# Poactuator_Connectors.net
KiCad netlist of a schematic drawn in Altium Designer
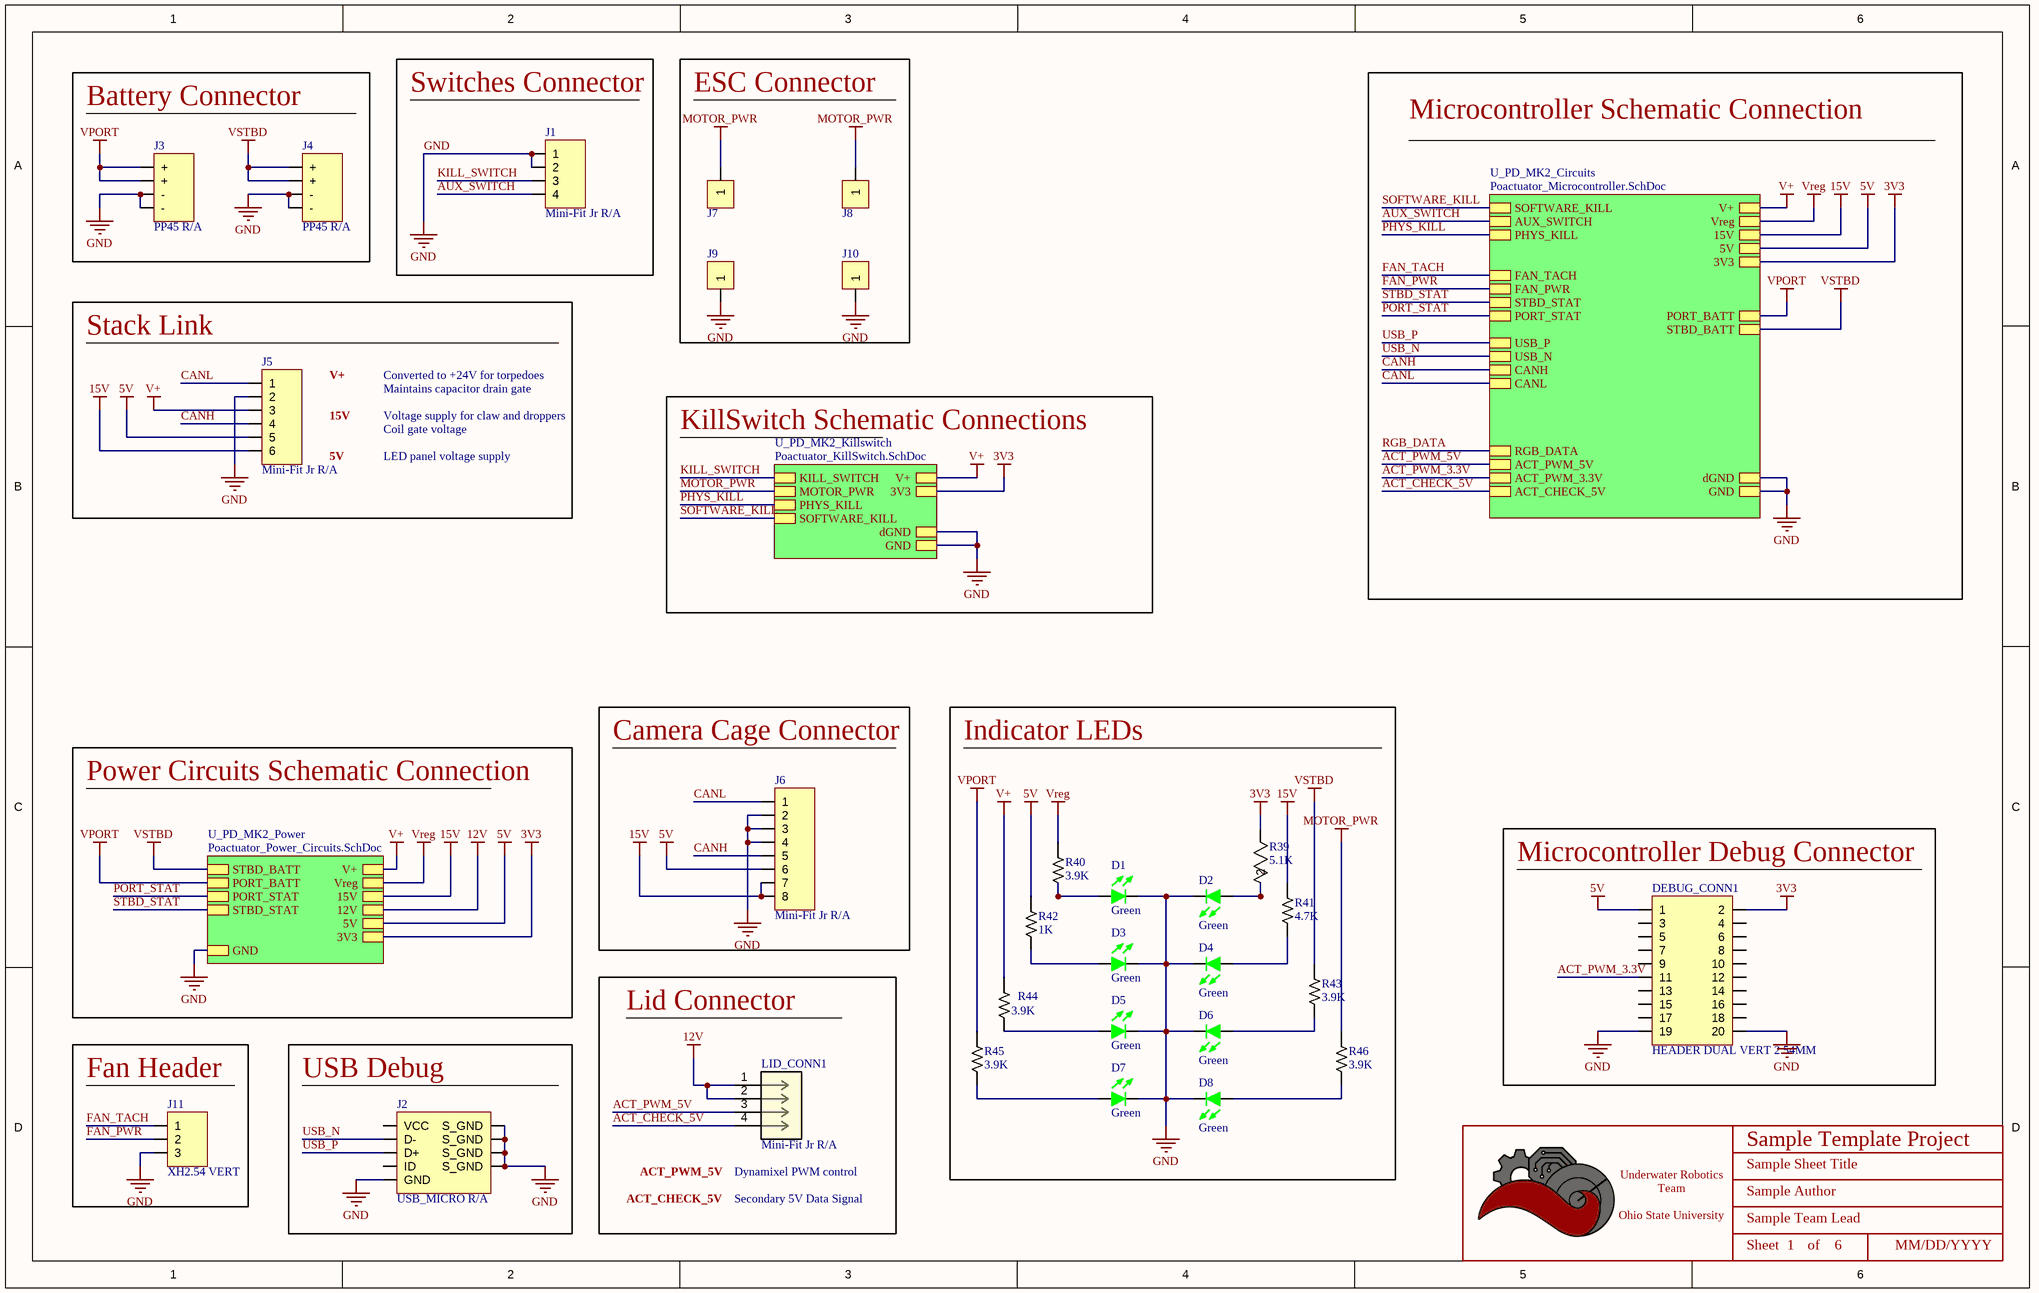
[diagram p0: Poactuator_Connectors.SchDoc]

(export (version "E")
  (design (tool "Eeschema 10.0.6"))
  (components
    (comp (ref "D1")
      (value "IN-S63AT5G")
      (footprint "LED_0603")
      (description "LED Green Vf= 3V If = 0.005A\r\nIN-S63AT5G")
      (fields (field (name "COLOR") "Green") (field (name "MADE BY") "Robert Pafford"))
      (libsource (lib "Diodes") (part "LED_Green_0603_3V"))
    )
    (comp (ref "D2")
      (value "IN-S63AT5G")
      (footprint "LED_0603")
      (description "LED Green Vf= 3V If = 0.005A\r\nIN-S63AT5G")
      (fields (field (name "COLOR") "Green") (field (name "MADE BY") "Robert Pafford"))
      (libsource (lib "Diodes") (part "LED_Green_0603_3V"))
    )
    (comp (ref "D3")
      (value "IN-S63AT5G")
      (footprint "LED_0603")
      (description "LED Green Vf= 3V If = 0.005A\r\nIN-S63AT5G")
      (fields (field (name "COLOR") "Green") (field (name "MADE BY") "Robert Pafford"))
      (libsource (lib "Diodes") (part "LED_Green_0603_3V"))
    )
    (comp (ref "D4")
      (value "IN-S63AT5G")
      (footprint "LED_0603")
      (description "LED Green Vf= 3V If = 0.005A\r\nIN-S63AT5G")
      (fields (field (name "COLOR") "Green") (field (name "MADE BY") "Robert Pafford"))
      (libsource (lib "Diodes") (part "LED_Green_0603_3V"))
    )
    (comp (ref "D5")
      (value "IN-S63AT5G")
      (footprint "LED_0603")
      (description "LED Green Vf= 3V If = 0.005A\r\nIN-S63AT5G")
      (fields (field (name "COLOR") "Green") (field (name "MADE BY") "Robert Pafford"))
      (libsource (lib "Diodes") (part "LED_Green_0603_3V"))
    )
    (comp (ref "D6")
      (value "IN-S63AT5G")
      (footprint "LED_0603")
      (description "LED Green Vf= 3V If = 0.005A\r\nIN-S63AT5G")
      (fields (field (name "COLOR") "Green") (field (name "MADE BY") "Robert Pafford"))
      (libsource (lib "Diodes") (part "LED_Green_0603_3V"))
    )
    (comp (ref "D7")
      (value "IN-S63AT5G")
      (footprint "LED_0603")
      (description "LED Green Vf= 3V If = 0.005A\r\nIN-S63AT5G")
      (fields (field (name "COLOR") "Green") (field (name "MADE BY") "Robert Pafford"))
      (libsource (lib "Diodes") (part "LED_Green_0603_3V"))
    )
    (comp (ref "D8")
      (value "IN-S63AT5G")
      (footprint "LED_0603")
      (description "LED Green Vf= 3V If = 0.005A\r\nIN-S63AT5G")
      (fields (field (name "COLOR") "Green") (field (name "MADE BY") "Robert Pafford"))
      (libsource (lib "Diodes") (part "LED_Green_0603_3V"))
    )
    (comp (ref "DEBUG_CONN1")
      (value "HEADER DUAL VERT 2.54MM")
      (footprint "HEADER_2x10PIN_2.54MM")
      (description "CONN HEADER VERT 20POS 2.54MM")
      (fields (field (name "MADE BY") "Tyson Nguyen"))
      (libsource (lib "Connectors") (part "HEADER_2x10PIN_2.54MM"))
    )
    (comp (ref "J1")
      (value "Mini-Fit Jr R/A")
      (footprint "CONN_MOLEX_MINIFIT JR_4 POS_R/A")
      (description "Molex Minifit Jr. 5569 \r\n4 Pos R/A Natural")
      (fields (field (name "MANUFACTURER") "Molex") (field (name "CREATED BY") "Flip B"))
      (libsource (lib "Connectors") (part "CONN_MOLEX_MINIFIT JR_4POS_R/A"))
    )
    (comp (ref "J2")
      (value "USB_MICRO R/A")
      (footprint "CONN_MINIUSB")
      (description "Amphenol Micro USB-B\r\nUSB2.0 5 Pin Right Angle SMD")
      (fields (field (name "MANUFACTURER") "Amphenol") (field (name "CREATED BY") "Flip B"))
      (libsource (lib "Connectors") (part "CONN_MICROUSB"))
    )
    (comp (ref "J3")
      (value "PP45 R/A")
      (footprint "CONN_ANDERSON_PP45_4 POS_R/A")
      (description "Anderson PP45\r\n4 Pos R/A Red/Black")
      (fields (field (name "MANUFACTURER") "Anderson") (field (name "CREATED BY") "Flip B"))
      (libsource (lib "Connectors") (part "CONN_ANDERSON_2x2_R/A"))
    )
    (comp (ref "J4")
      (value "PP45 R/A")
      (footprint "CONN_ANDERSON_PP45_4 POS_R/A")
      (description "Anderson PP45\r\n4 Pos R/A Red/Black")
      (fields (field (name "MANUFACTURER") "Anderson") (field (name "CREATED BY") "Flip B"))
      (libsource (lib "Connectors") (part "CONN_ANDERSON_2x2_R/A"))
    )
    (comp (ref "J5")
      (value "Mini-Fit Jr R/A")
      (footprint "CONN_MOLEX_MINIFIT JR_6 POS_R/A")
      (description "Molex Minifit Jr. 5569 \r\n6 Pos R/A Natural")
      (fields (field (name "MANUFACTURER") "Molex") (field (name "CREATED BY") "Flip B"))
      (libsource (lib "Connectors") (part "CONN_MOLEX_MINIFIT JR_6POS_R/A"))
    )
    (comp (ref "J6")
      (value "Mini-Fit Jr R/A")
      (footprint "CONN_MOLEX_MINIFIT JR_8 POS_R/A")
      (description "Molex Minifit Jr. 5569 \r\n8 Pos R/A Natural")
      (fields (field (name "MANUFACTURER") "Molex") (field (name "CREATED BY") "Flip B"))
      (libsource (lib "Connectors") (part "CONN_MOLEX_MINIFIT JR_8POS_R/A"))
    )
    (comp (ref "J7")
      (value "Redcube M4 Term 85A")
      (footprint "Redcube M4 Term 85A")
      (fields (field (name "CREATED BY") "Nahtan Ayer"))
      (libsource (lib "") (part "Redcube M4 Term 85A_1"))
    )
    (comp (ref "J8")
      (value "Redcube M4 Term 85A")
      (footprint "Redcube M4 Term 85A")
      (fields (field (name "CREATED BY") "Nahtan Ayer"))
      (libsource (lib "") (part "Redcube M4 Term 85A_1"))
    )
    (comp (ref "J9")
      (value "Redcube M4 Term 85A")
      (footprint "Redcube M4 Term 85A")
      (fields (field (name "CREATED BY") "Nahtan Ayer"))
      (libsource (lib "Connectors") (part "Redcube M4 Term 85A"))
    )
    (comp (ref "J10")
      (value "Redcube M4 Term 85A")
      (footprint "Redcube M4 Term 85A")
      (fields (field (name "CREATED BY") "Nahtan Ayer"))
      (libsource (lib "Connectors") (part "Redcube M4 Term 85A"))
    )
    (comp (ref "J11")
      (value "XH2.54 VERT")
      (footprint "CONN_JST_XH254_3POS_VERT")
      (description "JST XH 2.54mm Pitch 3 Pos Vertical")
      (fields (field (name "MANUFACTURER") "JST") (field (name "CREATED BY") "Robert P"))
      (libsource (lib "Connectors") (part "CONN_JST_XH254_3POS_VERT"))
    )
    (comp (ref "LID_CONN1")
      (value "Mini-Fit Jr R/A")
      (footprint "CONN HEADER R/A 4POS 4.2MM")
      (description "Mini-Fit Jr Connector Header Through Hole, Right Angle 4 position 0.165\" (4.20mm)")
      (fields (field (name "MANUFACTURER") "Molex") (field (name "CREATED BY") "Zach Ramsey"))
      (libsource (lib "Connectors") (part "CONN HEADER R/A 4POS 4.2MM"))
    )
    (comp (ref "R39")
      (value "5.1K")
      (footprint "RC0603N_PAN")
      (description "5.1 kOhms ±0.1% 0.1W, 1/10W Chip Resistor 0603 (1608 Metric) Automotive AEC-Q200 Thin Film")
      (fields
        (field (name "MANUFACTURER_PART_NUMBER") "ERA-3AEB512V_2")
        (field (name "COPYRIGHT") "Copyright (C) 2023 Ultra Librarian. All rights reserved.")
      )
      (libsource (lib "Resistors") (part "ERA-3AEB512V_2"))
    )
    (comp (ref "R40")
      (value "3.9k Ohm 5% 1/10W")
      (footprint "RESISTOR_0603")
      (description "RES 3.9k OHM 1% 1/10W 0603")
      (fields
        (field (name "TOLERANCE") "+/- 1%")
        (field (name "VALUE  (OHMS)") "3.9K")
        (field (name "MADE BY") "Robert Pafford")
      )
      (libsource (lib "Resistors") (part "RESISTOR_3.9K_0603"))
    )
    (comp (ref "R41")
      (value "4.7k Ohm 5% 1/10W")
      (footprint "RESISTOR_0603")
      (description "RES 4.7k OHM 5% 1/10W 0603")
      (fields
        (field (name "TOLERANCE") "+/- 5%")
        (field (name "VALUE  (OHMS)") "4.7K")
        (field (name "MADE BY") "Robert Pafford")
      )
      (libsource (lib "Resistors") (part "RESISTOR_4.7K_0603"))
    )
    (comp (ref "R42")
      (value "1k Ohm 5% 1/8W")
      (footprint "RESISTOR_0603")
      (description "RES 1k OHM 5% 1/8W 0603")
      (fields
        (field (name "TOLERANCE") "+/- 5%")
        (field (name "VALUE  (OHMS)") "1K")
        (field (name "MADE BY") "Robert Pafford")
      )
      (libsource (lib "Resistors") (part "RESISTOR_1K_0603"))
    )
    (comp (ref "R43")
      (value "3.9k Ohm 5% 1/10W")
      (footprint "RESISTOR_0603")
      (description "RES 3.9k OHM 1% 1/10W 0603")
      (fields
        (field (name "TOLERANCE") "+/- 1%")
        (field (name "VALUE  (OHMS)") "3.9K")
        (field (name "MADE BY") "Robert Pafford")
      )
      (libsource (lib "Resistors") (part "RESISTOR_3.9K_0603"))
    )
    (comp (ref "R44")
      (value "3.9k Ohm 5% 1/10W")
      (footprint "RESISTOR_0603")
      (description "RES 3.9k OHM 1% 1/10W 0603")
      (fields
        (field (name "TOLERANCE") "+/- 1%")
        (field (name "VALUE  (OHMS)") "3.9K")
        (field (name "MADE BY") "Robert Pafford")
      )
      (libsource (lib "Resistors") (part "RESISTOR_3.9K_0603"))
    )
    (comp (ref "R45")
      (value "3.9k Ohm 5% 1/10W")
      (footprint "RESISTOR_0603")
      (description "RES 3.9k OHM 1% 1/10W 0603")
      (fields
        (field (name "TOLERANCE") "+/- 1%")
        (field (name "VALUE  (OHMS)") "3.9K")
        (field (name "MADE BY") "Robert Pafford")
      )
      (libsource (lib "Resistors") (part "RESISTOR_3.9K_0603"))
    )
    (comp (ref "R46")
      (value "3.9k Ohm 5% 1/10W")
      (footprint "RESISTOR_0603")
      (description "RES 3.9k OHM 1% 1/10W 0603")
      (fields
        (field (name "TOLERANCE") "+/- 1%")
        (field (name "VALUE  (OHMS)") "3.9K")
        (field (name "MADE BY") "Robert Pafford")
      )
      (libsource (lib "Resistors") (part "RESISTOR_3.9K_0603"))
    )
  )
  (nets
    (net (code "1") (name "/ACT_CHECK_5V") (class "Default")
      (node (ref "LID_CONN1") (pin "4") (pinfunction "4_4") (pintype "passive"))
    )
    (net (code "2") (name "/ACT_PWM_3.3V") (class "Default")
      (node (ref "DEBUG_CONN1") (pin "11") (pinfunction "11_11") (pintype "passive"))
    )
    (net (code "3") (name "/ACT_PWM_5V") (class "Default")
      (node (ref "LID_CONN1") (pin "3") (pinfunction "3_3") (pintype "passive"))
    )
    (net (code "4") (name "/AUX_SWITCH") (class "Default")
      (node (ref "J1") (pin "4") (pinfunction "4_4") (pintype "passive"))
    )
    (net (code "5") (name "/CANH") (class "Default")
      (node (ref "J5") (pin "4") (pinfunction "4_4") (pintype "passive"))
      (node (ref "J6") (pin "5") (pinfunction "5_5") (pintype "passive"))
    )
    (net (code "6") (name "/CANL") (class "Default")
      (node (ref "J5") (pin "1") (pinfunction "1_1") (pintype "passive"))
      (node (ref "J6") (pin "1") (pinfunction "1_1") (pintype "passive"))
    )
    (net (code "7") (name "/FAN_PWR") (class "Default")
      (node (ref "J11") (pin "2") (pinfunction "2_2") (pintype "passive"))
    )
    (net (code "8") (name "/FAN_TACH") (class "Default")
      (node (ref "J11") (pin "1") (pinfunction "1_1") (pintype "passive"))
    )
    (net (code "9") (name "/KILL_SWITCH") (class "Default")
      (node (ref "J1") (pin "3") (pinfunction "3_3") (pintype "passive"))
    )
    (net (code "15") (name "/USB_N") (class "Default")
      (node (ref "J2") (pin "2") (pinfunction "D-_2") (pintype "passive"))
    )
    (net (code "16") (name "/USB_P") (class "Default")
      (node (ref "J2") (pin "3") (pinfunction "D+_3") (pintype "passive"))
    )
    (net (code "17") (name "3V3") (class "Default")
      (node (ref "DEBUG_CONN1") (pin "2") (pinfunction "2_2") (pintype "passive"))
      (node (ref "R39") (pin "1") (pinfunction "1_1") (pintype "passive"))
    )
    (net (code "18") (name "5V") (class "Default")
      (node (ref "DEBUG_CONN1") (pin "1") (pinfunction "1_1") (pintype "passive"))
      (node (ref "J5") (pin "5") (pinfunction "5_5") (pintype "passive"))
      (node (ref "J6") (pin "6") (pinfunction "6_6") (pintype "passive"))
      (node (ref "R42") (pin "1") (pinfunction "1_1") (pintype "passive"))
    )
    (net (code "19") (name "12V") (class "Default")
      (node (ref "LID_CONN1") (pin "1") (pinfunction "1_1") (pintype "passive"))
      (node (ref "LID_CONN1") (pin "2") (pinfunction "2_2") (pintype "passive"))
    )
    (net (code "20") (name "15V") (class "Default")
      (node (ref "J5") (pin "6") (pinfunction "6_6") (pintype "passive"))
      (node (ref "J6") (pin "7") (pinfunction "7_7") (pintype "passive"))
      (node (ref "J6") (pin "8") (pinfunction "8_8") (pintype "passive"))
      (node (ref "R41") (pin "1") (pinfunction "1_1") (pintype "passive"))
    )
    (net (code "21") (name "GND") (class "Default")
      (node (ref "D1") (pin "2") (pinfunction "2_2") (pintype "passive"))
      (node (ref "D2") (pin "2") (pinfunction "2_2") (pintype "passive"))
      (node (ref "D3") (pin "2") (pinfunction "2_2") (pintype "passive"))
      (node (ref "D4") (pin "2") (pinfunction "2_2") (pintype "passive"))
      (node (ref "D5") (pin "2") (pinfunction "2_2") (pintype "passive"))
      (node (ref "D6") (pin "2") (pinfunction "2_2") (pintype "passive"))
      (node (ref "D7") (pin "2") (pinfunction "2_2") (pintype "passive"))
      (node (ref "D8") (pin "2") (pinfunction "2_2") (pintype "passive"))
      (node (ref "DEBUG_CONN1") (pin "19") (pinfunction "19_19") (pintype "passive"))
      (node (ref "DEBUG_CONN1") (pin "20") (pinfunction "20_20") (pintype "passive"))
      (node (ref "J1") (pin "1") (pinfunction "1_1") (pintype "passive"))
      (node (ref "J1") (pin "2") (pinfunction "2_2") (pintype "passive"))
      (node (ref "J10") (pin "1") (pinfunction "1_1") (pintype "passive"))
      (node (ref "J11") (pin "3") (pinfunction "3_3") (pintype "passive"))
      (node (ref "J2") (pin "5") (pinfunction "GND_5") (pintype "passive"))
      (node (ref "J2") (pin "6") (pinfunction "S_GND_6") (pintype "passive"))
      (node (ref "J2") (pin "7") (pinfunction "S_GND_7") (pintype "passive"))
      (node (ref "J2") (pin "8") (pinfunction "S_GND_8") (pintype "passive"))
      (node (ref "J2") (pin "9") (pinfunction "S_GND_9") (pintype "passive"))
      (node (ref "J3") (pin "3") (pinfunction "-_3") (pintype "passive"))
      (node (ref "J3") (pin "4") (pinfunction "-_4") (pintype "passive"))
      (node (ref "J4") (pin "3") (pinfunction "-_3") (pintype "passive"))
      (node (ref "J4") (pin "4") (pinfunction "-_4") (pintype "passive"))
      (node (ref "J5") (pin "2") (pinfunction "2_2") (pintype "passive"))
      (node (ref "J6") (pin "2") (pinfunction "2_2") (pintype "passive"))
      (node (ref "J6") (pin "3") (pinfunction "3_3") (pintype "passive"))
      (node (ref "J6") (pin "4") (pinfunction "4_4") (pintype "passive"))
      (node (ref "J9") (pin "1") (pinfunction "1_1") (pintype "passive"))
    )
    (net (code "22") (name "MOTOR_PWR") (class "Default")
      (node (ref "J7") (pin "1") (pinfunction "1_1") (pintype "passive"))
      (node (ref "J8") (pin "1") (pinfunction "1_1") (pintype "passive"))
      (node (ref "R46") (pin "1") (pinfunction "1_1") (pintype "passive"))
    )
    (net (code "23") (name "Net-(D1-Pad1)") (class "Default")
      (node (ref "D1") (pin "1") (pinfunction "1_1") (pintype "passive"))
      (node (ref "R40") (pin "2") (pinfunction "2_2") (pintype "passive"))
    )
    (net (code "24") (name "Net-(D2-Pad1)") (class "Default")
      (node (ref "D2") (pin "1") (pinfunction "1_1") (pintype "passive"))
      (node (ref "R39") (pin "2") (pinfunction "2_2") (pintype "passive"))
    )
    (net (code "25") (name "Net-(D3-Pad1)") (class "Default")
      (node (ref "D3") (pin "1") (pinfunction "1_1") (pintype "passive"))
      (node (ref "R42") (pin "2") (pinfunction "2_2") (pintype "passive"))
    )
    (net (code "26") (name "Net-(D4-Pad1)") (class "Default")
      (node (ref "D4") (pin "1") (pinfunction "1_1") (pintype "passive"))
      (node (ref "R41") (pin "2") (pinfunction "2_2") (pintype "passive"))
    )
    (net (code "27") (name "Net-(D5-Pad1)") (class "Default")
      (node (ref "D5") (pin "1") (pinfunction "1_1") (pintype "passive"))
      (node (ref "R44") (pin "2") (pinfunction "2_2") (pintype "passive"))
    )
    (net (code "28") (name "Net-(D6-Pad1)") (class "Default")
      (node (ref "D6") (pin "1") (pinfunction "1_1") (pintype "passive"))
      (node (ref "R43") (pin "2") (pinfunction "2_2") (pintype "passive"))
    )
    (net (code "29") (name "Net-(D7-Pad1)") (class "Default")
      (node (ref "D7") (pin "1") (pinfunction "1_1") (pintype "passive"))
      (node (ref "R45") (pin "2") (pinfunction "2_2") (pintype "passive"))
    )
    (net (code "30") (name "Net-(D8-Pad1)") (class "Default")
      (node (ref "D8") (pin "1") (pinfunction "1_1") (pintype "passive"))
      (node (ref "R46") (pin "2") (pinfunction "2_2") (pintype "passive"))
    )
    (net (code "31") (name "V+") (class "Default")
      (node (ref "J5") (pin "3") (pinfunction "3_3") (pintype "passive"))
      (node (ref "R44") (pin "1") (pinfunction "1_1") (pintype "passive"))
    )
    (net (code "32") (name "VPORT") (class "Default")
      (node (ref "J3") (pin "1") (pinfunction "+_1") (pintype "passive"))
      (node (ref "J3") (pin "2") (pinfunction "+_2") (pintype "passive"))
      (node (ref "R45") (pin "1") (pinfunction "1_1") (pintype "passive"))
    )
    (net (code "33") (name "VSTBD") (class "Default")
      (node (ref "J4") (pin "1") (pinfunction "+_1") (pintype "passive"))
      (node (ref "J4") (pin "2") (pinfunction "+_2") (pintype "passive"))
      (node (ref "R43") (pin "1") (pinfunction "1_1") (pintype "passive"))
    )
    (net (code "34") (name "Vreg") (class "Default")
      (node (ref "R40") (pin "1") (pinfunction "1_1") (pintype "passive"))
    )
    (net (code "35") (name "unconnected-(DEBUG_CONN1-Pad3)") (class "Default")
      (node (ref "DEBUG_CONN1") (pin "3") (pinfunction "3_3") (pintype "passive"))
    )
    (net (code "36") (name "unconnected-(DEBUG_CONN1-Pad4)") (class "Default")
      (node (ref "DEBUG_CONN1") (pin "4") (pinfunction "4_4") (pintype "passive"))
    )
    (net (code "37") (name "unconnected-(DEBUG_CONN1-Pad5)") (class "Default")
      (node (ref "DEBUG_CONN1") (pin "5") (pinfunction "5_5") (pintype "passive"))
    )
    (net (code "38") (name "unconnected-(DEBUG_CONN1-Pad6)") (class "Default")
      (node (ref "DEBUG_CONN1") (pin "6") (pinfunction "6_6") (pintype "passive"))
    )
    (net (code "39") (name "unconnected-(DEBUG_CONN1-Pad7)") (class "Default")
      (node (ref "DEBUG_CONN1") (pin "7") (pinfunction "7_7") (pintype "passive"))
    )
    (net (code "40") (name "unconnected-(DEBUG_CONN1-Pad8)") (class "Default")
      (node (ref "DEBUG_CONN1") (pin "8") (pinfunction "8_8") (pintype "passive"))
    )
    (net (code "41") (name "unconnected-(DEBUG_CONN1-Pad9)") (class "Default")
      (node (ref "DEBUG_CONN1") (pin "9") (pinfunction "9_9") (pintype "passive"))
    )
    (net (code "42") (name "unconnected-(DEBUG_CONN1-Pad10)") (class "Default")
      (node (ref "DEBUG_CONN1") (pin "10") (pinfunction "10_10") (pintype "passive"))
    )
    (net (code "43") (name "unconnected-(DEBUG_CONN1-Pad12)") (class "Default")
      (node (ref "DEBUG_CONN1") (pin "12") (pinfunction "12_12") (pintype "passive"))
    )
    (net (code "44") (name "unconnected-(DEBUG_CONN1-Pad13)") (class "Default")
      (node (ref "DEBUG_CONN1") (pin "13") (pinfunction "13_13") (pintype "passive"))
    )
    (net (code "45") (name "unconnected-(DEBUG_CONN1-Pad14)") (class "Default")
      (node (ref "DEBUG_CONN1") (pin "14") (pinfunction "14_14") (pintype "passive"))
    )
    (net (code "46") (name "unconnected-(DEBUG_CONN1-Pad15)") (class "Default")
      (node (ref "DEBUG_CONN1") (pin "15") (pinfunction "15_15") (pintype "passive"))
    )
    (net (code "47") (name "unconnected-(DEBUG_CONN1-Pad16)") (class "Default")
      (node (ref "DEBUG_CONN1") (pin "16") (pinfunction "16_16") (pintype "passive"))
    )
    (net (code "48") (name "unconnected-(DEBUG_CONN1-Pad17)") (class "Default")
      (node (ref "DEBUG_CONN1") (pin "17") (pinfunction "17_17") (pintype "passive"))
    )
    (net (code "49") (name "unconnected-(DEBUG_CONN1-Pad18)") (class "Default")
      (node (ref "DEBUG_CONN1") (pin "18") (pinfunction "18_18") (pintype "passive"))
    )
    (net (code "50") (name "unconnected-(J2-ID-Pad4)") (class "Default")
      (node (ref "J2") (pin "4") (pinfunction "ID_4") (pintype "passive"))
    )
    (net (code "51") (name "unconnected-(J2-VCC-Pad1)") (class "Default")
      (node (ref "J2") (pin "1") (pinfunction "VCC_1") (pintype "passive"))
    )
  )
)
